# SCH_Plantcare_Module-v3_2024-10-24.net
KiCad netlist of a schematic drawn in EasyEDA
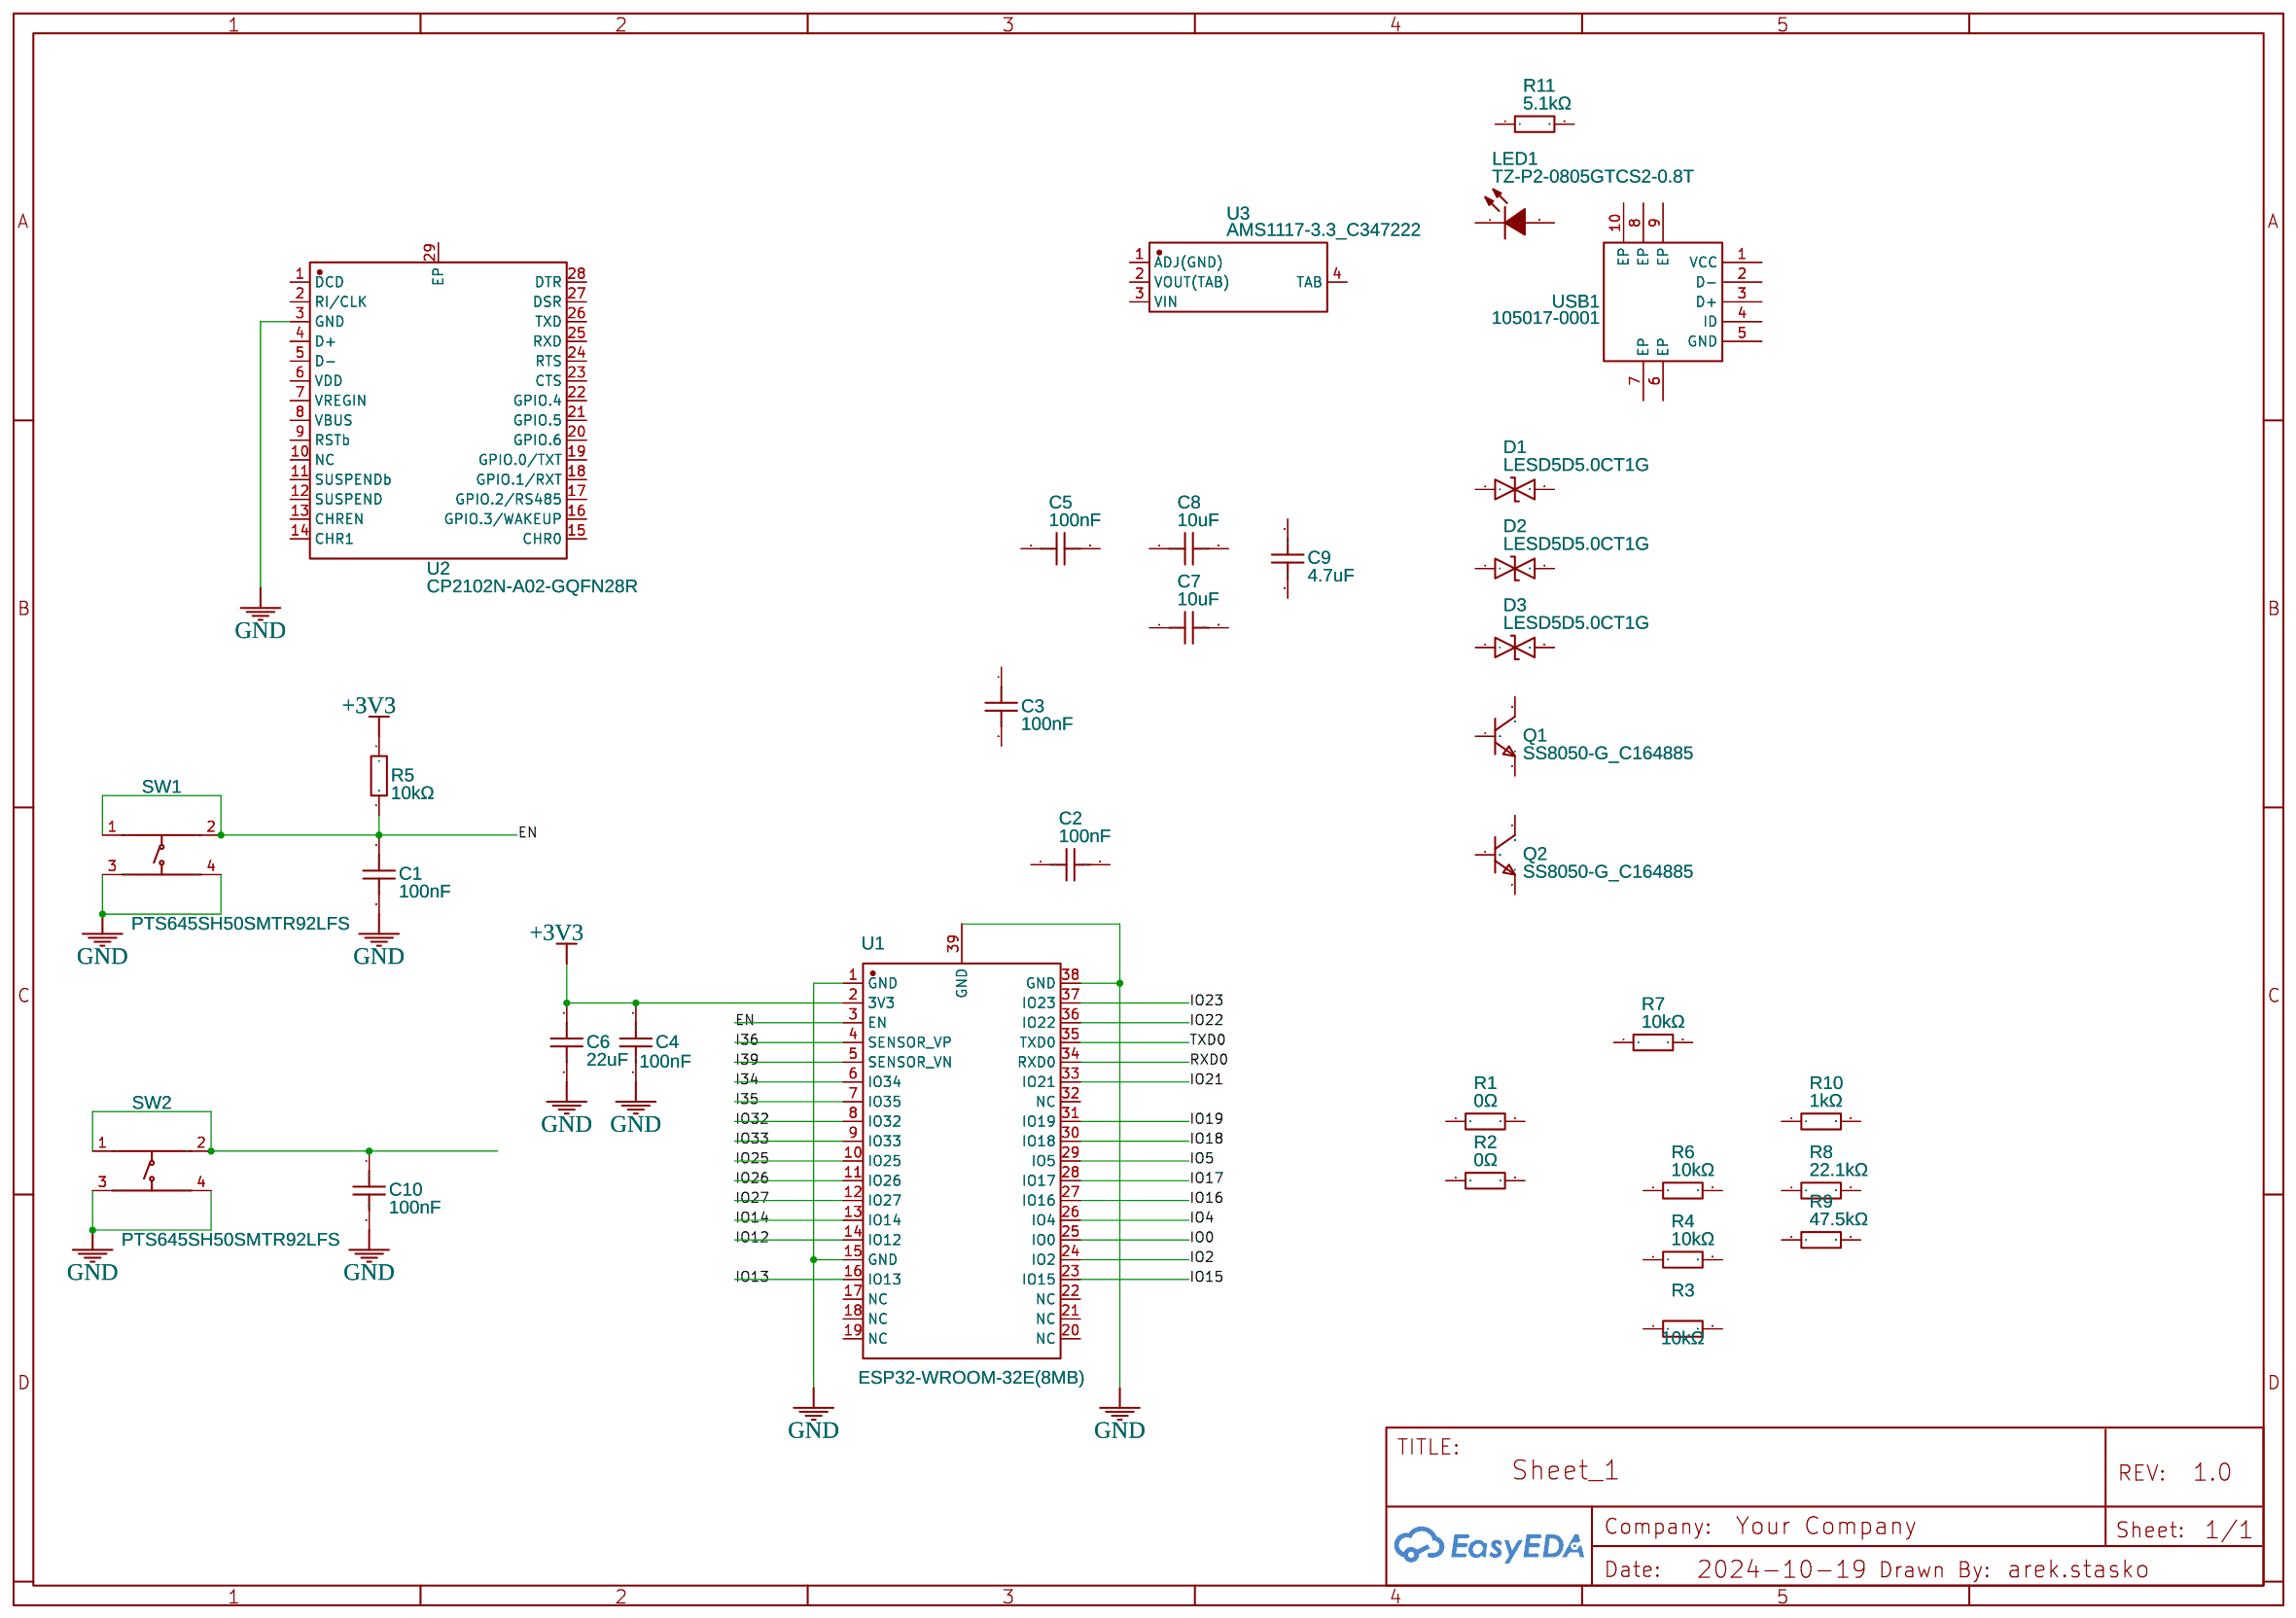
[diagram p0: schematic sheet]

(export (version "E")
  (design (tool "Eeschema 10.0.6"))
  (components
    (comp (ref "C1")
      (value "100nF")
      (fields
        (field (name "Manufacturer Part") "CL05B104KO5NNNC")
        (field (name "Manufacturer") "SAMSUNG(三星)")
      )
      (libsource (lib "") (part "CL05B104KO5NNNC_1"))
    )
    (comp (ref "C2")
      (value "100nF")
      (fields
        (field (name "Manufacturer Part") "CL05B104KO5NNNC")
        (field (name "Manufacturer") "SAMSUNG(三星)")
      )
      (libsource (lib "") (part "CL05B104KO5NNNC"))
    )
    (comp (ref "C3")
      (value "100nF")
      (fields
        (field (name "Manufacturer Part") "CL05B104KO5NNNC")
        (field (name "Manufacturer") "SAMSUNG(三星)")
      )
      (libsource (lib "") (part "CL05B104KO5NNNC_1"))
    )
    (comp (ref "C4")
      (value "100nF")
      (fields
        (field (name "Manufacturer Part") "CL05B104KO5NNNC")
        (field (name "Manufacturer") "SAMSUNG(三星)")
      )
      (libsource (lib "") (part "CL05B104KO5NNNC_1"))
    )
    (comp (ref "C5")
      (value "100nF")
      (fields
        (field (name "Manufacturer Part") "CL05B104KO5NNNC")
        (field (name "Manufacturer") "SAMSUNG(三星)")
      )
      (libsource (lib "") (part "CL05B104KO5NNNC"))
    )
    (comp (ref "C6")
      (value "22uF")
      (fields
        (field (name "Manufacturer Part") "CL21A226MAYNNNE")
        (field (name "Manufacturer") "SAMSUNG(三星)")
      )
      (libsource (lib "") (part "CL21A226MAYNNNE"))
    )
    (comp (ref "C7")
      (value "10uF")
      (fields
        (field (name "Manufacturer Part") "CL05A106MP5NUNC")
        (field (name "Manufacturer") "SAMSUNG(三星)")
      )
      (libsource (lib "") (part "CL05A106MP5NUNC_C315248"))
    )
    (comp (ref "C8")
      (value "10uF")
      (fields
        (field (name "Manufacturer Part") "CL05A106MP5NUNC")
        (field (name "Manufacturer") "SAMSUNG(三星)")
      )
      (libsource (lib "") (part "CL05A106MP5NUNC_C315248"))
    )
    (comp (ref "C9")
      (value "4.7uF")
      (fields
        (field (name "Manufacturer Part") "CL05A475KP5NRNC")
        (field (name "Manufacturer") "SAMSUNG(三星)")
      )
      (libsource (lib "") (part "CL05A475KP5NRNC"))
    )
    (comp (ref "C10")
      (value "100nF")
      (fields
        (field (name "Manufacturer Part") "CL05B104KO5NNNC")
        (field (name "Manufacturer") "SAMSUNG(三星)")
      )
      (libsource (lib "") (part "CL05B104KO5NNNC_1"))
    )
    (comp (ref "D1")
      (value "LESD5D5.0CT1G")
      (fields (field (name "Manufacturer") "LRC(乐山无线电)"))
      (libsource (lib "") (part "LESD5D5.0CT1G"))
    )
    (comp (ref "D2")
      (value "LESD5D5.0CT1G")
      (fields (field (name "Manufacturer") "LRC(乐山无线电)"))
      (libsource (lib "") (part "LESD5D5.0CT1G"))
    )
    (comp (ref "D3")
      (value "LESD5D5.0CT1G")
      (fields (field (name "Manufacturer") "LRC(乐山无线电)"))
      (libsource (lib "") (part "LESD5D5.0CT1G"))
    )
    (comp (ref "LED1")
      (value "TZ-P2-0805GTCS2-0.8T")
      (fields (field (name "Manufacturer") "TUOZHAN(拓展光电)"))
      (libsource (lib "") (part "TZ-P2-0805GTCS2-0.8T"))
    )
    (comp (ref "Q1")
      (value "SS8050-G_C164885")
      (fields (field (name "Manufacturer Part") "SS8050-G") (field (name "Manufacturer") "CJ(江苏长电/长晶)"))
      (libsource (lib "") (part "SS8050-G_C164885"))
    )
    (comp (ref "Q2")
      (value "SS8050-G_C164885")
      (fields (field (name "Manufacturer Part") "SS8050-G") (field (name "Manufacturer") "CJ(江苏长电/长晶)"))
      (libsource (lib "") (part "SS8050-G_C164885"))
    )
    (comp (ref "R1")
      (value "0Ω")
      (fields
        (field (name "Manufacturer Part") "0402WGF0000TCE")
        (field (name "Manufacturer") "UNI-ROYAL(厚声)")
      )
      (libsource (lib "") (part "0402WGF0000TCE"))
    )
    (comp (ref "R2")
      (value "0Ω")
      (fields
        (field (name "Manufacturer Part") "0402WGF0000TCE")
        (field (name "Manufacturer") "UNI-ROYAL(厚声)")
      )
      (libsource (lib "") (part "0402WGF0000TCE"))
    )
    (comp (ref "R3")
      (value "10kΩ")
      (fields
        (field (name "Manufacturer Part") "0402WGF1002TCE")
        (field (name "Manufacturer") "UNI-ROYAL(厚声)")
      )
      (libsource (lib "") (part "0402WGF1002TCE_1"))
    )
    (comp (ref "R4")
      (value "10kΩ")
      (fields
        (field (name "Manufacturer Part") "0402WGF1002TCE")
        (field (name "Manufacturer") "UNI-ROYAL(厚声)")
      )
      (libsource (lib "") (part "0402WGF1002TCE_1"))
    )
    (comp (ref "R5")
      (value "10kΩ")
      (fields
        (field (name "Manufacturer Part") "0402WGF1002TCE")
        (field (name "Manufacturer") "UNI-ROYAL(厚声)")
      )
      (libsource (lib "") (part "0402WGF1002TCE"))
    )
    (comp (ref "R6")
      (value "10kΩ")
      (fields
        (field (name "Manufacturer Part") "0402WGF1002TCE")
        (field (name "Manufacturer") "UNI-ROYAL(厚声)")
      )
      (libsource (lib "") (part "0402WGF1002TCE_1"))
    )
    (comp (ref "R7")
      (value "10kΩ")
      (fields
        (field (name "Manufacturer Part") "0402WGF1002TCE")
        (field (name "Manufacturer") "UNI-ROYAL(厚声)")
      )
      (libsource (lib "") (part "0402WGF1002TCE_1"))
    )
    (comp (ref "R8")
      (value "22.1kΩ")
      (fields
        (field (name "Manufacturer Part") "0402WGF2212TCE")
        (field (name "Manufacturer") "UNI-ROYAL(厚声)")
      )
      (libsource (lib "") (part "0402WGF2212TCE"))
    )
    (comp (ref "R9")
      (value "47.5kΩ")
      (fields
        (field (name "Manufacturer Part") "0402WGF4752TCE")
        (field (name "Manufacturer") "UNI-ROYAL(厚声)")
      )
      (libsource (lib "") (part "0402WGF4752TCE"))
    )
    (comp (ref "R10")
      (value "1kΩ")
      (fields
        (field (name "Manufacturer Part") "0402WGF1001TCE")
        (field (name "Manufacturer") "UNI-ROYAL(厚声)")
      )
      (libsource (lib "") (part "0402WGF1001TCE"))
    )
    (comp (ref "R11")
      (value "5.1kΩ")
      (fields
        (field (name "Manufacturer Part") "0402WGF5101TCE")
        (field (name "Manufacturer") "UNI-ROYAL(厚声)")
      )
      (libsource (lib "") (part "0402WGF5101TCE"))
    )
    (comp (ref "SW1")
      (value "PTS645SH50SMTR92LFS")
      (fields (field (name "Manufacturer") "C&K"))
      (libsource (lib "") (part "PTS645SH50SMTR92LFS"))
    )
    (comp (ref "SW2")
      (value "PTS645SH50SMTR92LFS")
      (fields (field (name "Manufacturer") "C&K"))
      (libsource (lib "") (part "PTS645SH50SMTR92LFS"))
    )
    (comp (ref "U1")
      (value "ESP32-WROOM-32E(8MB)")
      (fields
        (field (name "Manufacturer Part") "ESP32-WROOM-32E-N8")
        (field (name "Manufacturer") "ESPRESSIF(乐鑫)")
      )
      (libsource (lib "") (part "ESP32-WROOM-32E(8MB)"))
    )
    (comp (ref "U2")
      (value "CP2102N-A02-GQFN28R")
      (fields (field (name "Manufacturer") "SKYWORKS/SILICON LABS(芯科)"))
      (libsource (lib "") (part "CP2102N-A02-GQFN28R"))
    )
    (comp (ref "U3")
      (value "AMS1117-3.3_C347222")
      (fields (field (name "Manufacturer Part") "AMS1117-3.3") (field (name "Manufacturer") "UMW(友台半导体)"))
      (libsource (lib "") (part "AMS1117-3.3_C347222"))
    )
    (comp (ref "USB1")
      (value "105017-0001")
      (fields (field (name "Manufacturer Part") "1050170001") (field (name "Manufacturer") "MOLEX"))
      (libsource (lib "") (part "105017-0001"))
    )
  )
  (nets
    (net (code "1") (name "+3V3") (class "Default")
      (node (ref "C4") (pin "1") (pinfunction "1_1") (pintype "unspecified"))
      (node (ref "C6") (pin "1") (pinfunction "1_1") (pintype "unspecified"))
      (node (ref "R5") (pin "1") (pinfunction "1_1") (pintype "input"))
      (node (ref "U1") (pin "2") (pinfunction "3V3_2") (pintype "unspecified"))
    )
    (net (code "2") (name "/EN") (class "Default")
      (node (ref "C1") (pin "1") (pinfunction "1_1") (pintype "unspecified"))
      (node (ref "R5") (pin "2") (pinfunction "2_2") (pintype "input"))
      (node (ref "SW1") (pin "1") (pinfunction "1_1") (pintype "unspecified"))
      (node (ref "SW1") (pin "2") (pinfunction "2_2") (pintype "unspecified"))
      (node (ref "U1") (pin "3") (pinfunction "EN_3") (pintype "unspecified"))
    )
    (net (code "3") (name "/I34") (class "Default")
      (node (ref "U1") (pin "6") (pinfunction "IO34_6") (pintype "unspecified"))
    )
    (net (code "4") (name "/I35") (class "Default")
      (node (ref "U1") (pin "7") (pinfunction "IO35_7") (pintype "unspecified"))
    )
    (net (code "5") (name "/I36") (class "Default")
      (node (ref "U1") (pin "4") (pinfunction "SENSOR_VP_4") (pintype "unspecified"))
    )
    (net (code "6") (name "/I39") (class "Default")
      (node (ref "U1") (pin "5") (pinfunction "SENSOR_VN_5") (pintype "unspecified"))
    )
    (net (code "7") (name "/IO0") (class "Default")
      (node (ref "U1") (pin "25") (pinfunction "IO0_25") (pintype "unspecified"))
    )
    (net (code "8") (name "/IO2") (class "Default")
      (node (ref "U1") (pin "24") (pinfunction "IO2_24") (pintype "unspecified"))
    )
    (net (code "9") (name "/IO4") (class "Default")
      (node (ref "U1") (pin "26") (pinfunction "IO4_26") (pintype "unspecified"))
    )
    (net (code "10") (name "/IO5") (class "Default")
      (node (ref "U1") (pin "29") (pinfunction "IO5_29") (pintype "unspecified"))
    )
    (net (code "11") (name "/IO12") (class "Default")
      (node (ref "U1") (pin "14") (pinfunction "IO12_14") (pintype "unspecified"))
    )
    (net (code "12") (name "/IO13") (class "Default")
      (node (ref "U1") (pin "16") (pinfunction "IO13_16") (pintype "unspecified"))
    )
    (net (code "13") (name "/IO14") (class "Default")
      (node (ref "U1") (pin "13") (pinfunction "IO14_13") (pintype "unspecified"))
    )
    (net (code "14") (name "/IO15") (class "Default")
      (node (ref "U1") (pin "23") (pinfunction "IO15_23") (pintype "unspecified"))
    )
    (net (code "15") (name "/IO16") (class "Default")
      (node (ref "U1") (pin "27") (pinfunction "IO16_27") (pintype "unspecified"))
    )
    (net (code "16") (name "/IO17") (class "Default")
      (node (ref "U1") (pin "28") (pinfunction "IO17_28") (pintype "unspecified"))
    )
    (net (code "17") (name "/IO18") (class "Default")
      (node (ref "U1") (pin "30") (pinfunction "IO18_30") (pintype "unspecified"))
    )
    (net (code "18") (name "/IO19") (class "Default")
      (node (ref "U1") (pin "31") (pinfunction "IO19_31") (pintype "unspecified"))
    )
    (net (code "19") (name "/IO21") (class "Default")
      (node (ref "U1") (pin "33") (pinfunction "IO21_33") (pintype "unspecified"))
    )
    (net (code "20") (name "/IO22") (class "Default")
      (node (ref "U1") (pin "36") (pinfunction "IO22_36") (pintype "unspecified"))
    )
    (net (code "21") (name "/IO23") (class "Default")
      (node (ref "U1") (pin "37") (pinfunction "IO23_37") (pintype "unspecified"))
    )
    (net (code "22") (name "/IO25") (class "Default")
      (node (ref "U1") (pin "10") (pinfunction "IO25_10") (pintype "unspecified"))
    )
    (net (code "23") (name "/IO26") (class "Default")
      (node (ref "U1") (pin "11") (pinfunction "IO26_11") (pintype "unspecified"))
    )
    (net (code "24") (name "/IO27") (class "Default")
      (node (ref "U1") (pin "12") (pinfunction "IO27_12") (pintype "unspecified"))
    )
    (net (code "25") (name "/IO32") (class "Default")
      (node (ref "U1") (pin "8") (pinfunction "IO32_8") (pintype "unspecified"))
    )
    (net (code "26") (name "/IO33") (class "Default")
      (node (ref "U1") (pin "9") (pinfunction "IO33_9") (pintype "unspecified"))
    )
    (net (code "27") (name "/RXD0") (class "Default")
      (node (ref "U1") (pin "34") (pinfunction "RXD0_34") (pintype "unspecified"))
    )
    (net (code "28") (name "/TXD0") (class "Default")
      (node (ref "U1") (pin "35") (pinfunction "TXD0_35") (pintype "unspecified"))
    )
    (net (code "29") (name "GND") (class "Default")
      (node (ref "C1") (pin "2") (pinfunction "2_2") (pintype "unspecified"))
      (node (ref "C10") (pin "2") (pinfunction "2_2") (pintype "unspecified"))
      (node (ref "C4") (pin "2") (pinfunction "2_2") (pintype "unspecified"))
      (node (ref "C6") (pin "2") (pinfunction "2_2") (pintype "unspecified"))
      (node (ref "SW1") (pin "3") (pinfunction "3_3") (pintype "unspecified"))
      (node (ref "SW1") (pin "4") (pinfunction "4_4") (pintype "unspecified"))
      (node (ref "SW2") (pin "3") (pinfunction "3_3") (pintype "unspecified"))
      (node (ref "SW2") (pin "4") (pinfunction "4_4") (pintype "unspecified"))
      (node (ref "U1") (pin "1") (pinfunction "GND_1") (pintype "unspecified"))
      (node (ref "U1") (pin "15") (pinfunction "GND_15") (pintype "unspecified"))
      (node (ref "U1") (pin "38") (pinfunction "GND_38") (pintype "unspecified"))
      (node (ref "U1") (pin "39") (pinfunction "GND_39") (pintype "unspecified"))
      (node (ref "U2") (pin "3") (pinfunction "GND_3") (pintype "unspecified"))
    )
    (net (code "30") (name "Net-(C10-Pad1)") (class "Default")
      (node (ref "C10") (pin "1") (pinfunction "1_1") (pintype "unspecified"))
      (node (ref "SW2") (pin "1") (pinfunction "1_1") (pintype "unspecified"))
      (node (ref "SW2") (pin "2") (pinfunction "2_2") (pintype "unspecified"))
    )
    (net (code "31") (name "unconnected-(C2-Pad1)") (class "Default")
      (node (ref "C2") (pin "1") (pinfunction "1_1") (pintype "unspecified"))
    )
    (net (code "32") (name "unconnected-(C2-Pad2)") (class "Default")
      (node (ref "C2") (pin "2") (pinfunction "2_2") (pintype "unspecified"))
    )
    (net (code "33") (name "unconnected-(C3-Pad1)") (class "Default")
      (node (ref "C3") (pin "1") (pinfunction "1_1") (pintype "unspecified"))
    )
    (net (code "34") (name "unconnected-(C3-Pad2)") (class "Default")
      (node (ref "C3") (pin "2") (pinfunction "2_2") (pintype "unspecified"))
    )
    (net (code "35") (name "unconnected-(C5-Pad1)") (class "Default")
      (node (ref "C5") (pin "1") (pinfunction "1_1") (pintype "unspecified"))
    )
    (net (code "36") (name "unconnected-(C5-Pad2)") (class "Default")
      (node (ref "C5") (pin "2") (pinfunction "2_2") (pintype "unspecified"))
    )
    (net (code "37") (name "unconnected-(C7-Pad1)") (class "Default")
      (node (ref "C7") (pin "1") (pinfunction "1_1") (pintype "unspecified"))
    )
    (net (code "38") (name "unconnected-(C7-Pad2)") (class "Default")
      (node (ref "C7") (pin "2") (pinfunction "2_2") (pintype "unspecified"))
    )
    (net (code "39") (name "unconnected-(C8-Pad1)") (class "Default")
      (node (ref "C8") (pin "1") (pinfunction "1_1") (pintype "unspecified"))
    )
    (net (code "40") (name "unconnected-(C8-Pad2)") (class "Default")
      (node (ref "C8") (pin "2") (pinfunction "2_2") (pintype "unspecified"))
    )
    (net (code "41") (name "unconnected-(C9-Pad1)") (class "Default")
      (node (ref "C9") (pin "1") (pinfunction "1_1") (pintype "unspecified"))
    )
    (net (code "42") (name "unconnected-(C9-Pad2)") (class "Default")
      (node (ref "C9") (pin "2") (pinfunction "2_2") (pintype "unspecified"))
    )
    (net (code "43") (name "unconnected-(D1-Pad1)") (class "Default")
      (node (ref "D1") (pin "1") (pinfunction "1_1") (pintype "unspecified"))
    )
    (net (code "44") (name "unconnected-(D1-Pad2)") (class "Default")
      (node (ref "D1") (pin "2") (pinfunction "2_2") (pintype "unspecified"))
    )
    (net (code "45") (name "unconnected-(D2-Pad1)") (class "Default")
      (node (ref "D2") (pin "1") (pinfunction "1_1") (pintype "unspecified"))
    )
    (net (code "46") (name "unconnected-(D2-Pad2)") (class "Default")
      (node (ref "D2") (pin "2") (pinfunction "2_2") (pintype "unspecified"))
    )
    (net (code "47") (name "unconnected-(D3-Pad1)") (class "Default")
      (node (ref "D3") (pin "1") (pinfunction "1_1") (pintype "unspecified"))
    )
    (net (code "48") (name "unconnected-(D3-Pad2)") (class "Default")
      (node (ref "D3") (pin "2") (pinfunction "2_2") (pintype "unspecified"))
    )
    (net (code "49") (name "unconnected-(LED1-+-Pad2)") (class "Default")
      (node (ref "LED1") (pin "2") (pinfunction "+_2") (pintype "unspecified"))
    )
    (net (code "50") (name "unconnected-(LED1---Pad1)") (class "Default")
      (node (ref "LED1") (pin "1") (pinfunction "-_1") (pintype "unspecified"))
    )
    (net (code "51") (name "unconnected-(Q1-B-Pad1)") (class "Default")
      (node (ref "Q1") (pin "1") (pinfunction "B_1") (pintype "unspecified"))
    )
    (net (code "52") (name "unconnected-(Q1-C-Pad3)") (class "Default")
      (node (ref "Q1") (pin "3") (pinfunction "C_3") (pintype "unspecified"))
    )
    (net (code "53") (name "unconnected-(Q1-E-Pad2)") (class "Default")
      (node (ref "Q1") (pin "2") (pinfunction "E_2") (pintype "unspecified"))
    )
    (net (code "54") (name "unconnected-(Q2-B-Pad1)") (class "Default")
      (node (ref "Q2") (pin "1") (pinfunction "B_1") (pintype "unspecified"))
    )
    (net (code "55") (name "unconnected-(Q2-C-Pad3)") (class "Default")
      (node (ref "Q2") (pin "3") (pinfunction "C_3") (pintype "unspecified"))
    )
    (net (code "56") (name "unconnected-(Q2-E-Pad2)") (class "Default")
      (node (ref "Q2") (pin "2") (pinfunction "E_2") (pintype "unspecified"))
    )
    (net (code "57") (name "unconnected-(R1-Pad1)") (class "Default")
      (node (ref "R1") (pin "1") (pinfunction "1_1") (pintype "input"))
    )
    (net (code "58") (name "unconnected-(R1-Pad2)") (class "Default")
      (node (ref "R1") (pin "2") (pinfunction "2_2") (pintype "input"))
    )
    (net (code "59") (name "unconnected-(R2-Pad1)") (class "Default")
      (node (ref "R2") (pin "1") (pinfunction "1_1") (pintype "input"))
    )
    (net (code "60") (name "unconnected-(R2-Pad2)") (class "Default")
      (node (ref "R2") (pin "2") (pinfunction "2_2") (pintype "input"))
    )
    (net (code "61") (name "unconnected-(R3-Pad1)") (class "Default")
      (node (ref "R3") (pin "1") (pinfunction "1_1") (pintype "input"))
    )
    (net (code "62") (name "unconnected-(R3-Pad2)") (class "Default")
      (node (ref "R3") (pin "2") (pinfunction "2_2") (pintype "input"))
    )
    (net (code "63") (name "unconnected-(R4-Pad1)") (class "Default")
      (node (ref "R4") (pin "1") (pinfunction "1_1") (pintype "input"))
    )
    (net (code "64") (name "unconnected-(R4-Pad2)") (class "Default")
      (node (ref "R4") (pin "2") (pinfunction "2_2") (pintype "input"))
    )
    (net (code "65") (name "unconnected-(R6-Pad1)") (class "Default")
      (node (ref "R6") (pin "1") (pinfunction "1_1") (pintype "input"))
    )
    (net (code "66") (name "unconnected-(R6-Pad2)") (class "Default")
      (node (ref "R6") (pin "2") (pinfunction "2_2") (pintype "input"))
    )
    (net (code "67") (name "unconnected-(R7-Pad1)") (class "Default")
      (node (ref "R7") (pin "1") (pinfunction "1_1") (pintype "input"))
    )
    (net (code "68") (name "unconnected-(R7-Pad2)") (class "Default")
      (node (ref "R7") (pin "2") (pinfunction "2_2") (pintype "input"))
    )
    (net (code "69") (name "unconnected-(R8-Pad1)") (class "Default")
      (node (ref "R8") (pin "1") (pinfunction "1_1") (pintype "input"))
    )
    (net (code "70") (name "unconnected-(R8-Pad2)") (class "Default")
      (node (ref "R8") (pin "2") (pinfunction "2_2") (pintype "input"))
    )
    (net (code "71") (name "unconnected-(R9-Pad1)") (class "Default")
      (node (ref "R9") (pin "1") (pinfunction "1_1") (pintype "input"))
    )
    (net (code "72") (name "unconnected-(R9-Pad2)") (class "Default")
      (node (ref "R9") (pin "2") (pinfunction "2_2") (pintype "input"))
    )
    (net (code "73") (name "unconnected-(R10-Pad1)") (class "Default")
      (node (ref "R10") (pin "1") (pinfunction "1_1") (pintype "input"))
    )
    (net (code "74") (name "unconnected-(R10-Pad2)") (class "Default")
      (node (ref "R10") (pin "2") (pinfunction "2_2") (pintype "input"))
    )
    (net (code "75") (name "unconnected-(R11-Pad1)") (class "Default")
      (node (ref "R11") (pin "1") (pinfunction "1_1") (pintype "input"))
    )
    (net (code "76") (name "unconnected-(R11-Pad2)") (class "Default")
      (node (ref "R11") (pin "2") (pinfunction "2_2") (pintype "input"))
    )
    (net (code "77") (name "unconnected-(U1-NC-Pad17)") (class "Default")
      (node (ref "U1") (pin "17") (pinfunction "NC_17") (pintype "unspecified"))
    )
    (net (code "78") (name "unconnected-(U1-NC-Pad18)") (class "Default")
      (node (ref "U1") (pin "18") (pinfunction "NC_18") (pintype "unspecified"))
    )
    (net (code "79") (name "unconnected-(U1-NC-Pad19)") (class "Default")
      (node (ref "U1") (pin "19") (pinfunction "NC_19") (pintype "unspecified"))
    )
    (net (code "80") (name "unconnected-(U1-NC-Pad20)") (class "Default")
      (node (ref "U1") (pin "20") (pinfunction "NC_20") (pintype "unspecified"))
    )
    (net (code "81") (name "unconnected-(U1-NC-Pad21)") (class "Default")
      (node (ref "U1") (pin "21") (pinfunction "NC_21") (pintype "unspecified"))
    )
    (net (code "82") (name "unconnected-(U1-NC-Pad22)") (class "Default")
      (node (ref "U1") (pin "22") (pinfunction "NC_22") (pintype "unspecified"))
    )
    (net (code "83") (name "unconnected-(U1-NC-Pad32)") (class "Default")
      (node (ref "U1") (pin "32") (pinfunction "NC_32") (pintype "unspecified"))
    )
    (net (code "84") (name "unconnected-(U2-CHR0-Pad15)") (class "Default")
      (node (ref "U2") (pin "15") (pinfunction "CHR0_15") (pintype "unspecified"))
    )
    (net (code "85") (name "unconnected-(U2-CHR1-Pad14)") (class "Default")
      (node (ref "U2") (pin "14") (pinfunction "CHR1_14") (pintype "unspecified"))
    )
    (net (code "86") (name "unconnected-(U2-CHREN-Pad13)") (class "Default")
      (node (ref "U2") (pin "13") (pinfunction "CHREN_13") (pintype "unspecified"))
    )
    (net (code "87") (name "unconnected-(U2-CTS-Pad23)") (class "Default")
      (node (ref "U2") (pin "23") (pinfunction "CTS_23") (pintype "unspecified"))
    )
    (net (code "88") (name "unconnected-(U2-D+-Pad4)") (class "Default")
      (node (ref "U2") (pin "4") (pinfunction "D+_4") (pintype "unspecified"))
    )
    (net (code "89") (name "unconnected-(U2-D--Pad5)") (class "Default")
      (node (ref "U2") (pin "5") (pinfunction "D-_5") (pintype "unspecified"))
    )
    (net (code "90") (name "unconnected-(U2-DCD-Pad1)") (class "Default")
      (node (ref "U2") (pin "1") (pinfunction "DCD_1") (pintype "unspecified"))
    )
    (net (code "91") (name "unconnected-(U2-DSR-Pad27)") (class "Default")
      (node (ref "U2") (pin "27") (pinfunction "DSR_27") (pintype "unspecified"))
    )
    (net (code "92") (name "unconnected-(U2-DTR-Pad28)") (class "Default")
      (node (ref "U2") (pin "28") (pinfunction "DTR_28") (pintype "unspecified"))
    )
    (net (code "93") (name "unconnected-(U2-EP-Pad29)") (class "Default")
      (node (ref "U2") (pin "29") (pinfunction "EP_29") (pintype "unspecified"))
    )
    (net (code "94") (name "unconnected-(U2-GPIO.0{slash}TXT-Pad19)") (class "Default")
      (node (ref "U2") (pin "19") (pinfunction "GPIO.0/TXT_19") (pintype "unspecified"))
    )
    (net (code "95") (name "unconnected-(U2-GPIO.1{slash}RXT-Pad18)") (class "Default")
      (node (ref "U2") (pin "18") (pinfunction "GPIO.1/RXT_18") (pintype "unspecified"))
    )
    (net (code "96") (name "unconnected-(U2-GPIO.2{slash}RS485-Pad17)") (class "Default")
      (node (ref "U2") (pin "17") (pinfunction "GPIO.2/RS485_17") (pintype "unspecified"))
    )
    (net (code "97") (name "unconnected-(U2-GPIO.3{slash}WAKEUP-Pad16)") (class "Default")
      (node (ref "U2") (pin "16") (pinfunction "GPIO.3/WAKEUP_16") (pintype "unspecified"))
    )
    (net (code "98") (name "unconnected-(U2-GPIO.4-Pad22)") (class "Default")
      (node (ref "U2") (pin "22") (pinfunction "GPIO.4_22") (pintype "unspecified"))
    )
    (net (code "99") (name "unconnected-(U2-GPIO.5-Pad21)") (class "Default")
      (node (ref "U2") (pin "21") (pinfunction "GPIO.5_21") (pintype "unspecified"))
    )
    (net (code "100") (name "unconnected-(U2-GPIO.6-Pad20)") (class "Default")
      (node (ref "U2") (pin "20") (pinfunction "GPIO.6_20") (pintype "unspecified"))
    )
    (net (code "101") (name "unconnected-(U2-NC-Pad10)") (class "Default")
      (node (ref "U2") (pin "10") (pinfunction "NC_10") (pintype "unspecified"))
    )
    (net (code "102") (name "unconnected-(U2-RI{slash}CLK-Pad2)") (class "Default")
      (node (ref "U2") (pin "2") (pinfunction "RI/CLK_2") (pintype "unspecified"))
    )
    (net (code "103") (name "unconnected-(U2-RSTb-Pad9)") (class "Default")
      (node (ref "U2") (pin "9") (pinfunction "RSTb_9") (pintype "unspecified"))
    )
    (net (code "104") (name "unconnected-(U2-RTS-Pad24)") (class "Default")
      (node (ref "U2") (pin "24") (pinfunction "RTS_24") (pintype "unspecified"))
    )
    (net (code "105") (name "unconnected-(U2-RXD-Pad25)") (class "Default")
      (node (ref "U2") (pin "25") (pinfunction "RXD_25") (pintype "unspecified"))
    )
    (net (code "106") (name "unconnected-(U2-SUSPEND-Pad12)") (class "Default")
      (node (ref "U2") (pin "12") (pinfunction "SUSPEND_12") (pintype "unspecified"))
    )
    (net (code "107") (name "unconnected-(U2-SUSPENDb-Pad11)") (class "Default")
      (node (ref "U2") (pin "11") (pinfunction "SUSPENDb_11") (pintype "unspecified"))
    )
    (net (code "108") (name "unconnected-(U2-TXD-Pad26)") (class "Default")
      (node (ref "U2") (pin "26") (pinfunction "TXD_26") (pintype "unspecified"))
    )
    (net (code "109") (name "unconnected-(U2-VBUS-Pad8)") (class "Default")
      (node (ref "U2") (pin "8") (pinfunction "VBUS_8") (pintype "unspecified"))
    )
    (net (code "110") (name "unconnected-(U2-VDD-Pad6)") (class "Default")
      (node (ref "U2") (pin "6") (pinfunction "VDD_6") (pintype "unspecified"))
    )
    (net (code "111") (name "unconnected-(U2-VREGIN-Pad7)") (class "Default")
      (node (ref "U2") (pin "7") (pinfunction "VREGIN_7") (pintype "unspecified"))
    )
    (net (code "112") (name "unconnected-(U3-ADJ(GND)-Pad1)") (class "Default")
      (node (ref "U3") (pin "1") (pinfunction "ADJ(GND)_1") (pintype "unspecified"))
    )
    (net (code "113") (name "unconnected-(U3-TAB-Pad4)") (class "Default")
      (node (ref "U3") (pin "4") (pinfunction "TAB_4") (pintype "unspecified"))
    )
    (net (code "114") (name "unconnected-(U3-VIN-Pad3)") (class "Default")
      (node (ref "U3") (pin "3") (pinfunction "VIN_3") (pintype "unspecified"))
    )
    (net (code "115") (name "unconnected-(U3-VOUT(TAB)-Pad2)") (class "Default")
      (node (ref "U3") (pin "2") (pinfunction "VOUT(TAB)_2") (pintype "unspecified"))
    )
    (net (code "116") (name "unconnected-(USB1-D+-Pad3)") (class "Default")
      (node (ref "USB1") (pin "3") (pinfunction "D+_3") (pintype "unspecified"))
    )
    (net (code "117") (name "unconnected-(USB1-D--Pad2)") (class "Default")
      (node (ref "USB1") (pin "2") (pinfunction "D-_2") (pintype "unspecified"))
    )
    (net (code "118") (name "unconnected-(USB1-EP-Pad6)") (class "Default")
      (node (ref "USB1") (pin "6") (pinfunction "EP_6") (pintype "unspecified"))
    )
    (net (code "119") (name "unconnected-(USB1-EP-Pad7)") (class "Default")
      (node (ref "USB1") (pin "7") (pinfunction "EP_7") (pintype "unspecified"))
    )
    (net (code "120") (name "unconnected-(USB1-EP-Pad8)") (class "Default")
      (node (ref "USB1") (pin "8") (pinfunction "EP_8") (pintype "unspecified"))
    )
    (net (code "121") (name "unconnected-(USB1-EP-Pad9)") (class "Default")
      (node (ref "USB1") (pin "9") (pinfunction "EP_9") (pintype "unspecified"))
    )
    (net (code "122") (name "unconnected-(USB1-EP-Pad10)") (class "Default")
      (node (ref "USB1") (pin "10") (pinfunction "EP_10") (pintype "unspecified"))
    )
    (net (code "123") (name "unconnected-(USB1-GND-Pad5)") (class "Default")
      (node (ref "USB1") (pin "5") (pinfunction "GND_5") (pintype "unspecified"))
    )
    (net (code "124") (name "unconnected-(USB1-ID-Pad4)") (class "Default")
      (node (ref "USB1") (pin "4") (pinfunction "ID_4") (pintype "unspecified"))
    )
    (net (code "125") (name "unconnected-(USB1-VCC-Pad1)") (class "Default")
      (node (ref "USB1") (pin "1") (pinfunction "VCC_1") (pintype "unspecified"))
    )
  )
)
